# secondary-power-board.net
KiCad netlist of a schematic drawn in EAGLE
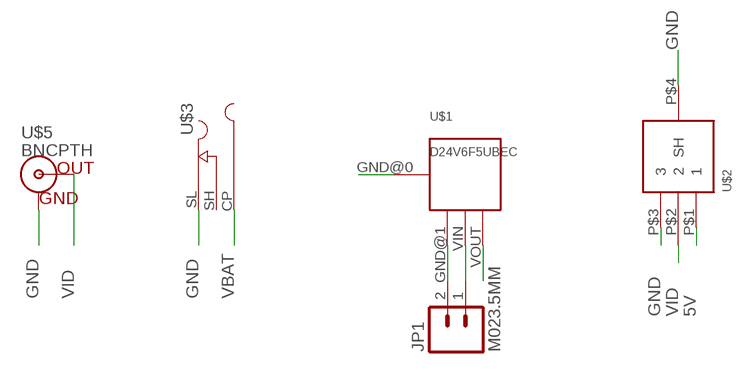
[diagram p0: schematic, sheet 1]

(export (version "E")
  (design (tool "Eeschema 10.0.6"))
  (components
    (comp (ref "JP1")
      (value "M023.5MM")
      (footprint "eagle-import:SCREWTERMINAL-3.5MM-2")
      (libsource (lib "eagle-import") (part "M023.5MM"))
    )
    (comp (ref "U$1")
      (value "D24V6F5UBEC")
      (footprint "eagle-import:P2177")
      (libsource (lib "eagle-import") (part "D24V6F5UBEC"))
    )
    (comp (ref "U$2")
      (value "TRA3M")
      (footprint "eagle-import:TRA3M")
      (libsource (lib "eagle-import") (part "TRA3M"))
    )
    (comp (ref "U$3")
      (value "L722RAS")
      (footprint "eagle-import:L722RAS")
      (libsource (lib "eagle-import") (part "L722RAS"))
    )
    (comp (ref "U$5")
      (value "BNCPTH")
      (footprint "eagle-import:BNC")
      (libsource (lib "eagle-import") (part "BNCPTH"))
    )
  )
  (nets
    (net (code "1") (name "/5V") (class "Default")
      (node (ref "U$1") (pin "VOUT") (pinfunction "P$4_VOUT") (pintype "bidirectional"))
      (node (ref "U$2") (pin "P$1") (pinfunction "1_P$1") (pintype "bidirectional"))
    )
    (net (code "2") (name "/GND") (class "Default")
      (node (ref "JP1") (pin "2") (pinfunction "2_2") (pintype "passive"))
      (node (ref "U$1") (pin "GND@0") (pinfunction "P$1_GND@0") (pintype "bidirectional"))
      (node (ref "U$1") (pin "GND@1") (pinfunction "P$2_GND@1") (pintype "bidirectional"))
      (node (ref "U$2") (pin "P$3") (pinfunction "3_P$3") (pintype "bidirectional"))
      (node (ref "U$2") (pin "P$4") (pinfunction "SH_P$4") (pintype "bidirectional"))
      (node (ref "U$3") (pin "SL") (pinfunction "SLEEVE_SL") (pintype "bidirectional"))
      (node (ref "U$5") (pin "GND") (pinfunction "GND_GND") (pintype "bidirectional"))
    )
    (net (code "3") (name "/VBAT") (class "Default")
      (node (ref "JP1") (pin "1") (pinfunction "1_1") (pintype "passive"))
      (node (ref "U$1") (pin "VIN") (pinfunction "P$3_VIN") (pintype "bidirectional"))
      (node (ref "U$3") (pin "CP") (pinfunction "CENTRE_CP") (pintype "bidirectional"))
    )
    (net (code "4") (name "/VID") (class "Default")
      (node (ref "U$2") (pin "P$2") (pinfunction "2_P$2") (pintype "bidirectional"))
      (node (ref "U$5") (pin "S") (pinfunction "OUT_S") (pintype "bidirectional"))
    )
    (net (code "5") (name "unconnected-(U$3-SHUNT-PadSH)") (class "Default")
      (node (ref "U$3") (pin "SH") (pinfunction "SHUNT_SH") (pintype "bidirectional"))
    )
  )
)
